# design.net
KiCad netlist of a schematic drawn in Altium Designer
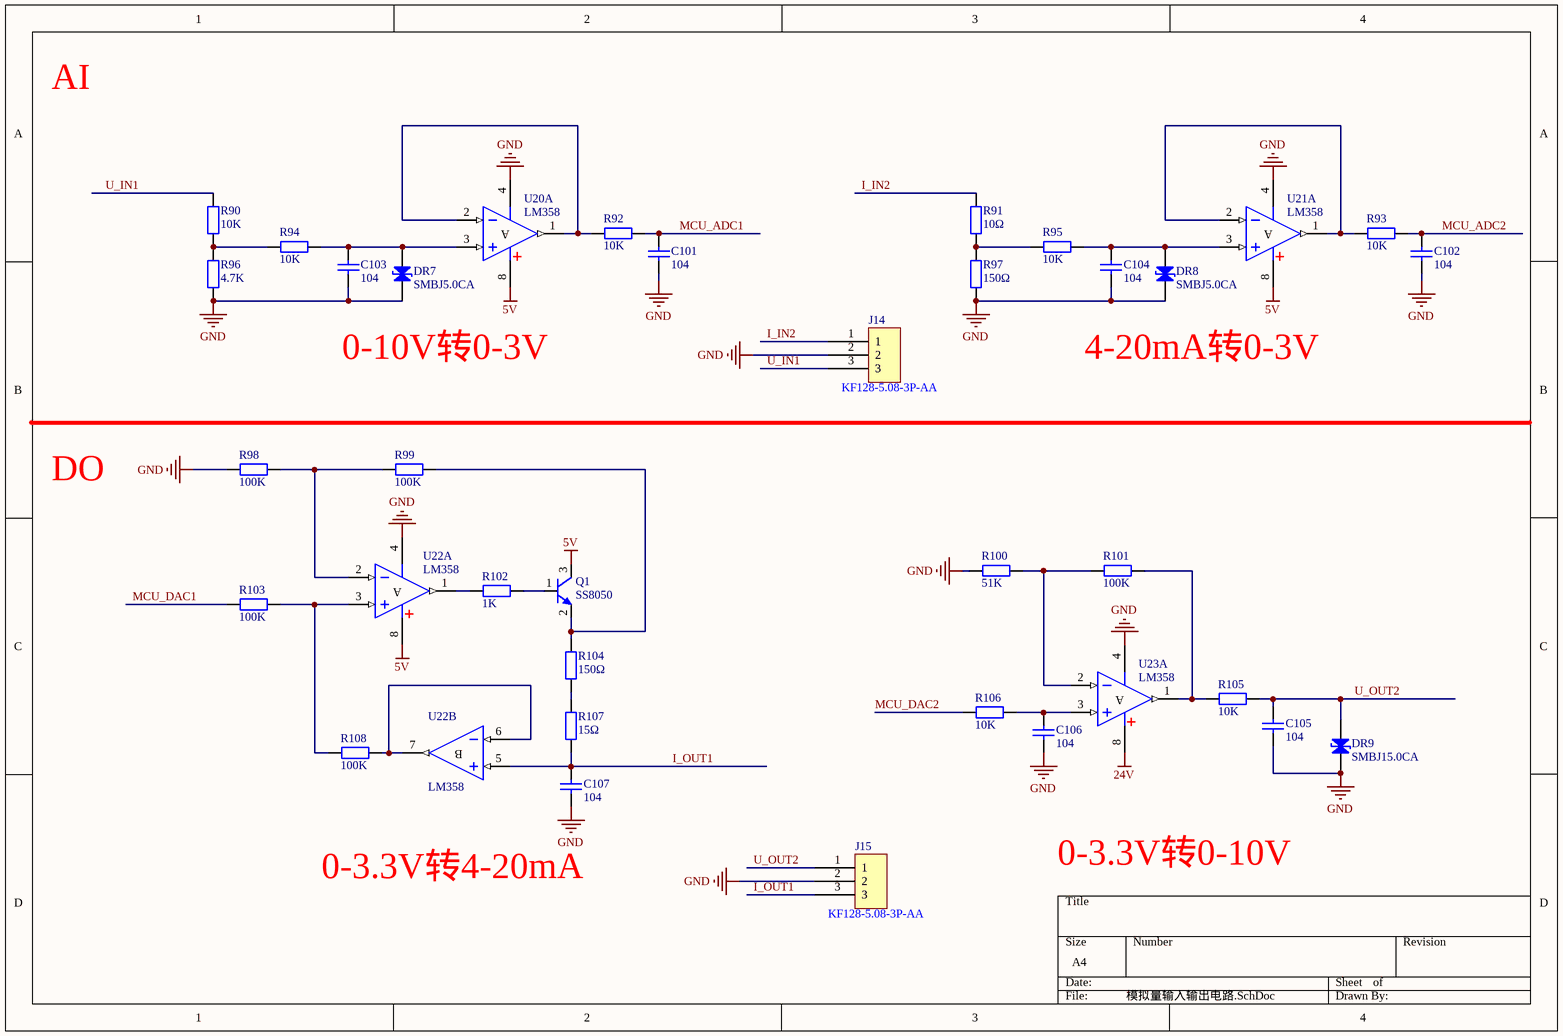
[diagram p0: 模拟量输入输出电路.SchDoc]

(export (version "E")
  (design (tool "Eeschema 10.0.6"))
  (components
    (comp (ref "C101")
      (value "104")
      (footprint "C 0603_L")
      (description "0603贴片电容")
      (fields (field (name "PUBLISHER") "Altium Limited"))
      (libsource (lib "STM32_PLC_20251215") (part "Cap"))
    )
    (comp (ref "C102")
      (value "104")
      (footprint "C 0603_L")
      (description "0603贴片电容")
      (fields (field (name "PUBLISHER") "Altium Limited"))
      (libsource (lib "STM32_PLC_20251215") (part "Cap"))
    )
    (comp (ref "C103")
      (value "104")
      (footprint "C 0603_L")
      (description "0603贴片电容")
      (fields (field (name "PUBLISHER") "Altium Limited"))
      (libsource (lib "STM32_PLC_20251215") (part "Cap"))
    )
    (comp (ref "C104")
      (value "104")
      (footprint "C 0603_L")
      (description "0603贴片电容")
      (fields (field (name "PUBLISHER") "Altium Limited"))
      (libsource (lib "STM32_PLC_20251215") (part "Cap"))
    )
    (comp (ref "C105")
      (value "104")
      (footprint "C 0603_L")
      (description "0603贴片电容")
      (fields (field (name "PUBLISHER") "Altium Limited"))
      (libsource (lib "STM32_PLC_20251215") (part "Cap"))
    )
    (comp (ref "C106")
      (value "104")
      (footprint "C 0603_L")
      (description "0603贴片电容")
      (fields (field (name "PUBLISHER") "Altium Limited"))
      (libsource (lib "STM32_PLC_20251215") (part "Cap"))
    )
    (comp (ref "C107")
      (value "104")
      (footprint "C 0603_L")
      (description "0603贴片电容")
      (fields (field (name "PUBLISHER") "Altium Limited"))
      (libsource (lib "STM32_PLC_20251215") (part "Cap"))
    )
    (comp (ref "DR7")
      (value "SMBJ5.0CA")
      (footprint "SMB")
      (description "SMA，瞬态电压抑制二极管")
      (fields (field (name "版权归属") "源创客"))
      (libsource (lib "STM32_PLC_20251215") (part "TVS"))
    )
    (comp (ref "DR8")
      (value "SMBJ5.0CA")
      (footprint "SMB")
      (description "SMA，瞬态电压抑制二极管")
      (fields (field (name "版权归属") "源创客"))
      (libsource (lib "STM32_PLC_20251215") (part "TVS"))
    )
    (comp (ref "DR9")
      (value "SMBJ15.0CA")
      (footprint "SMB")
      (description "SMA，瞬态电压抑制二极管")
      (fields (field (name "版权归属") "源创客"))
      (libsource (lib "STM32_PLC_20251215") (part "TVS"))
    )
    (comp (ref "J14")
      (value "KF128-5.08-3P-AA")
      (footprint "KF128-5.08-3P")
      (description "KF128-5.08-3P-AA端座")
      (fields (field (name "MANUFACTURER") "KEFA(科发)"))
      (libsource (lib "STM32_PLC_20251215") (part "KF128-5.08-3P-AA"))
    )
    (comp (ref "J15")
      (value "KF128-5.08-3P-AA")
      (footprint "KF128-5.08-3P")
      (description "KF128-5.08-3P-AA端座")
      (fields (field (name "MANUFACTURER") "KEFA(科发)"))
      (libsource (lib "STM32_PLC_20251215") (part "KF128-5.08-3P-AA"))
    )
    (comp (ref "Q1")
      (value "SS8050")
      (footprint "SOT-23_S8050")
      (description "NPN三极管")
      (fields (field (name "版权归属") "源创客"))
      (libsource (lib "STM32_PLC_20251215") (part "S8050"))
    )
    (comp (ref "R90")
      (value "10K")
      (footprint "R 0603_L")
      (description "C0603贴片电阻")
      (fields (field (name "版权归属") "源创客"))
      (libsource (lib "STM32_PLC_20251215") (part "Res"))
    )
    (comp (ref "R91")
      (value "10Ω")
      (footprint "R 0603_L")
      (description "C0603贴片电阻")
      (fields (field (name "版权归属") "源创客"))
      (libsource (lib "STM32_PLC_20251215") (part "Res"))
    )
    (comp (ref "R92")
      (value "10K")
      (footprint "R 0603_L")
      (description "C0603贴片电阻")
      (fields (field (name "版权归属") "源创客"))
      (libsource (lib "STM32_PLC_20251215") (part "Res"))
    )
    (comp (ref "R93")
      (value "10K")
      (footprint "R 0603_L")
      (description "C0603贴片电阻")
      (fields (field (name "版权归属") "源创客"))
      (libsource (lib "STM32_PLC_20251215") (part "Res"))
    )
    (comp (ref "R94")
      (value "10K")
      (footprint "R 0603_L")
      (description "C0603贴片电阻")
      (fields (field (name "版权归属") "源创客"))
      (libsource (lib "STM32_PLC_20251215") (part "Res"))
    )
    (comp (ref "R95")
      (value "10K")
      (footprint "R 0603_L")
      (description "C0603贴片电阻")
      (fields (field (name "版权归属") "源创客"))
      (libsource (lib "STM32_PLC_20251215") (part "Res"))
    )
    (comp (ref "R96")
      (value "4.7K")
      (footprint "R 0603_L")
      (description "C0603贴片电阻")
      (fields (field (name "版权归属") "源创客"))
      (libsource (lib "STM32_PLC_20251215") (part "Res"))
    )
    (comp (ref "R97")
      (value "150Ω")
      (footprint "R 0603_L")
      (description "C0603贴片电阻")
      (fields (field (name "版权归属") "源创客"))
      (libsource (lib "STM32_PLC_20251215") (part "Res"))
    )
    (comp (ref "R98")
      (value "100K")
      (footprint "R 0603_L")
      (description "C0603贴片电阻")
      (fields (field (name "版权归属") "源创客"))
      (libsource (lib "STM32_PLC_20251215") (part "Res"))
    )
    (comp (ref "R99")
      (value "100K")
      (footprint "R 0603_L")
      (description "C0603贴片电阻")
      (fields (field (name "版权归属") "源创客"))
      (libsource (lib "STM32_PLC_20251215") (part "Res"))
    )
    (comp (ref "R100")
      (value "51K")
      (footprint "R 0603_L")
      (description "C0603贴片电阻")
      (fields (field (name "版权归属") "源创客"))
      (libsource (lib "STM32_PLC_20251215") (part "Res"))
    )
    (comp (ref "R101")
      (value "100K")
      (footprint "R 0603_L")
      (description "C0603贴片电阻")
      (fields (field (name "版权归属") "源创客"))
      (libsource (lib "STM32_PLC_20251215") (part "Res"))
    )
    (comp (ref "R102")
      (value "1K")
      (footprint "R 0603_L")
      (description "C0603贴片电阻")
      (fields (field (name "版权归属") "源创客"))
      (libsource (lib "STM32_PLC_20251215") (part "Res"))
    )
    (comp (ref "R103")
      (value "100K")
      (footprint "R 0603_L")
      (description "C0603贴片电阻")
      (fields (field (name "版权归属") "源创客"))
      (libsource (lib "STM32_PLC_20251215") (part "Res"))
    )
    (comp (ref "R104")
      (value "150Ω")
      (footprint "R 0603_L")
      (description "0603贴片电阻")
      (fields (field (name "版权归属") "源创客"))
      (libsource (lib "STM32_PLC_20251215") (part "Res"))
    )
    (comp (ref "R105")
      (value "10K")
      (footprint "R 0603_L")
      (description "C0603贴片电阻")
      (fields (field (name "版权归属") "源创客"))
      (libsource (lib "STM32_PLC_20251215") (part "Res"))
    )
    (comp (ref "R106")
      (value "10K")
      (footprint "R 0603_L")
      (description "C0603贴片电阻")
      (fields (field (name "版权归属") "源创客"))
      (libsource (lib "STM32_PLC_20251215") (part "Res"))
    )
    (comp (ref "R107")
      (value "15Ω")
      (footprint "R 0603_L")
      (description "0603贴片电阻")
      (fields (field (name "版权归属") "源创客"))
      (libsource (lib "STM32_PLC_20251215") (part "Res"))
    )
    (comp (ref "R108")
      (value "100K")
      (footprint "R 0603_L")
      (description "C0603贴片电阻")
      (fields (field (name "版权归属") "源创客"))
      (libsource (lib "STM32_PLC_20251215") (part "Res"))
    )
    (comp (ref "U20")
      (value "LM358")
      (footprint "SOP8")
      (description "双路运放")
      (fields (field (name "版权归属") "源创客"))
      (libsource (lib "STM32_PLC_20251215") (part "LM358"))
    )
    (comp (ref "U21")
      (value "LM358")
      (footprint "SOP8")
      (description "双路运放")
      (fields (field (name "版权归属") "源创客"))
      (libsource (lib "STM32_PLC_20251215") (part "LM358"))
    )
    (comp (ref "U22")
      (value "LM358")
      (footprint "SOP8")
      (description "双路运放")
      (fields (field (name "版权归属") "源创客"))
      (libsource (lib "STM32_PLC_20251215") (part "LM358"))
    )
    (comp (ref "U23")
      (value "LM358")
      (footprint "SOP8")
      (description "双路运放")
      (fields (field (name "版权归属") "源创客"))
      (libsource (lib "STM32_PLC_20251215") (part "LM358"))
    )
  )
  (nets
    (net (code "1") (name "/I_IN2") (class "Default")
      (node (ref "J14") (pin "1") (pinfunction "1_1") (pintype "passive"))
      (node (ref "R91") (pin "2") (pinfunction "2_2") (pintype "passive"))
    )
    (net (code "2") (name "/I_OUT1") (class "Default")
      (node (ref "C107") (pin "2") (pinfunction "2_2") (pintype "passive"))
      (node (ref "J15") (pin "3") (pinfunction "3_3") (pintype "passive"))
      (node (ref "R107") (pin "2") (pinfunction "2_2") (pintype "passive"))
      (node (ref "U22") (pin "5") (pinfunction "IN+_5") (pintype "input"))
    )
    (net (code "3") (name "/MCU_ADC1") (class "Default")
      (node (ref "C101") (pin "2") (pinfunction "2_2") (pintype "passive"))
      (node (ref "R92") (pin "1") (pinfunction "1_1") (pintype "passive"))
    )
    (net (code "4") (name "/MCU_ADC2") (class "Default")
      (node (ref "C102") (pin "2") (pinfunction "2_2") (pintype "passive"))
      (node (ref "R93") (pin "1") (pinfunction "1_1") (pintype "passive"))
    )
    (net (code "5") (name "/MCU_DAC1") (class "Default")
      (node (ref "R103") (pin "2") (pinfunction "2_2") (pintype "passive"))
    )
    (net (code "6") (name "/MCU_DAC2") (class "Default")
      (node (ref "R106") (pin "2") (pinfunction "2_2") (pintype "passive"))
    )
    (net (code "7") (name "/U_IN1") (class "Default")
      (node (ref "J14") (pin "3") (pinfunction "3_3") (pintype "passive"))
      (node (ref "R90") (pin "2") (pinfunction "2_2") (pintype "passive"))
    )
    (net (code "8") (name "/U_OUT2") (class "Default")
      (node (ref "C105") (pin "2") (pinfunction "2_2") (pintype "passive"))
      (node (ref "DR9") (pin "1") (pinfunction "A_1") (pintype "passive"))
      (node (ref "J15") (pin "1") (pinfunction "1_1") (pintype "passive"))
      (node (ref "R105") (pin "1") (pinfunction "1_1") (pintype "passive"))
    )
    (net (code "9") (name "5V") (class "Default")
      (node (ref "Q1") (pin "3") (pinfunction "C_3") (pintype "passive"))
      (node (ref "U20") (pin "8") (pinfunction "V+_8") (pintype "power_in"))
      (node (ref "U21") (pin "8") (pinfunction "V+_8") (pintype "power_in"))
      (node (ref "U22") (pin "8") (pinfunction "V+_8") (pintype "power_in"))
    )
    (net (code "10") (name "24V") (class "Default")
      (node (ref "U23") (pin "8") (pinfunction "V+_8") (pintype "power_in"))
    )
    (net (code "11") (name "GND") (class "Default")
      (node (ref "C101") (pin "1") (pinfunction "1_1") (pintype "passive"))
      (node (ref "C102") (pin "1") (pinfunction "1_1") (pintype "passive"))
      (node (ref "C103") (pin "1") (pinfunction "1_1") (pintype "passive"))
      (node (ref "C104") (pin "1") (pinfunction "1_1") (pintype "passive"))
      (node (ref "C105") (pin "1") (pinfunction "1_1") (pintype "passive"))
      (node (ref "C106") (pin "1") (pinfunction "1_1") (pintype "passive"))
      (node (ref "C107") (pin "1") (pinfunction "1_1") (pintype "passive"))
      (node (ref "DR7") (pin "2") (pinfunction "K_2") (pintype "passive"))
      (node (ref "DR8") (pin "2") (pinfunction "K_2") (pintype "passive"))
      (node (ref "DR9") (pin "2") (pinfunction "K_2") (pintype "passive"))
      (node (ref "J14") (pin "2") (pinfunction "2_2") (pintype "passive"))
      (node (ref "J15") (pin "2") (pinfunction "2_2") (pintype "passive"))
      (node (ref "R100") (pin "2") (pinfunction "2_2") (pintype "passive"))
      (node (ref "R96") (pin "1") (pinfunction "1_1") (pintype "passive"))
      (node (ref "R97") (pin "1") (pinfunction "1_1") (pintype "passive"))
      (node (ref "R98") (pin "2") (pinfunction "2_2") (pintype "passive"))
      (node (ref "U20") (pin "4") (pinfunction "V-_4") (pintype "power_in"))
      (node (ref "U21") (pin "4") (pinfunction "V-_4") (pintype "power_in"))
      (node (ref "U22") (pin "4") (pinfunction "V-_4") (pintype "power_in"))
      (node (ref "U23") (pin "4") (pinfunction "V-_4") (pintype "power_in"))
    )
    (net (code "12") (name "Net-(DR7-A)") (class "Default")
      (node (ref "C103") (pin "2") (pinfunction "2_2") (pintype "passive"))
      (node (ref "DR7") (pin "1") (pinfunction "A_1") (pintype "passive"))
      (node (ref "R94") (pin "1") (pinfunction "1_1") (pintype "passive"))
      (node (ref "U20") (pin "3") (pinfunction "IN+_3") (pintype "input"))
    )
    (net (code "13") (name "Net-(DR8-A)") (class "Default")
      (node (ref "C104") (pin "2") (pinfunction "2_2") (pintype "passive"))
      (node (ref "DR8") (pin "1") (pinfunction "A_1") (pintype "passive"))
      (node (ref "R95") (pin "1") (pinfunction "1_1") (pintype "passive"))
      (node (ref "U21") (pin "3") (pinfunction "IN+_3") (pintype "input"))
    )
    (net (code "14") (name "Net-(Q1-B)") (class "Default")
      (node (ref "Q1") (pin "1") (pinfunction "B_1") (pintype "passive"))
      (node (ref "R102") (pin "1") (pinfunction "1_1") (pintype "passive"))
    )
    (net (code "15") (name "Net-(Q1-E)") (class "Default")
      (node (ref "Q1") (pin "2") (pinfunction "E_2") (pintype "passive"))
      (node (ref "R104") (pin "1") (pinfunction "1_1") (pintype "passive"))
      (node (ref "R99") (pin "1") (pinfunction "1_1") (pintype "passive"))
    )
    (net (code "16") (name "Net-(R90-Pad1)") (class "Default")
      (node (ref "R90") (pin "1") (pinfunction "1_1") (pintype "passive"))
      (node (ref "R94") (pin "2") (pinfunction "2_2") (pintype "passive"))
      (node (ref "R96") (pin "2") (pinfunction "2_2") (pintype "passive"))
    )
    (net (code "17") (name "Net-(R91-Pad1)") (class "Default")
      (node (ref "R91") (pin "1") (pinfunction "1_1") (pintype "passive"))
      (node (ref "R95") (pin "2") (pinfunction "2_2") (pintype "passive"))
      (node (ref "R97") (pin "2") (pinfunction "2_2") (pintype "passive"))
    )
    (net (code "18") (name "Net-(R104-Pad2)") (class "Default")
      (node (ref "R104") (pin "2") (pinfunction "2_2") (pintype "passive"))
      (node (ref "R107") (pin "1") (pinfunction "1_1") (pintype "passive"))
    )
    (net (code "19") (name "Net-(U20A-IN-)") (class "Default")
      (node (ref "R92") (pin "2") (pinfunction "2_2") (pintype "passive"))
      (node (ref "U20") (pin "1") (pinfunction "OUT_1") (pintype "output"))
      (node (ref "U20") (pin "2") (pinfunction "IN-_2") (pintype "input"))
    )
    (net (code "20") (name "Net-(U21A-IN-)") (class "Default")
      (node (ref "R93") (pin "2") (pinfunction "2_2") (pintype "passive"))
      (node (ref "U21") (pin "1") (pinfunction "OUT_1") (pintype "output"))
      (node (ref "U21") (pin "2") (pinfunction "IN-_2") (pintype "input"))
    )
    (net (code "21") (name "Net-(U22A-IN+)") (class "Default")
      (node (ref "R103") (pin "1") (pinfunction "1_1") (pintype "passive"))
      (node (ref "R108") (pin "2") (pinfunction "2_2") (pintype "passive"))
      (node (ref "U22") (pin "3") (pinfunction "IN+_3") (pintype "input"))
    )
    (net (code "22") (name "Net-(U22A-IN-)") (class "Default")
      (node (ref "R98") (pin "1") (pinfunction "1_1") (pintype "passive"))
      (node (ref "R99") (pin "2") (pinfunction "2_2") (pintype "passive"))
      (node (ref "U22") (pin "2") (pinfunction "IN-_2") (pintype "input"))
    )
    (net (code "23") (name "Net-(U22A-OUT)") (class "Default")
      (node (ref "R102") (pin "2") (pinfunction "2_2") (pintype "passive"))
      (node (ref "U22") (pin "1") (pinfunction "OUT_1") (pintype "output"))
    )
    (net (code "24") (name "Net-(U22B-IN-)") (class "Default")
      (node (ref "R108") (pin "1") (pinfunction "1_1") (pintype "passive"))
      (node (ref "U22") (pin "6") (pinfunction "IN-_6") (pintype "input"))
      (node (ref "U22") (pin "7") (pinfunction "OUT_7") (pintype "output"))
    )
    (net (code "25") (name "Net-(U23A-IN+)") (class "Default")
      (node (ref "C106") (pin "2") (pinfunction "2_2") (pintype "passive"))
      (node (ref "R106") (pin "1") (pinfunction "1_1") (pintype "passive"))
      (node (ref "U23") (pin "3") (pinfunction "IN+_3") (pintype "input"))
    )
    (net (code "26") (name "Net-(U23A-IN-)") (class "Default")
      (node (ref "R100") (pin "1") (pinfunction "1_1") (pintype "passive"))
      (node (ref "R101") (pin "2") (pinfunction "2_2") (pintype "passive"))
      (node (ref "U23") (pin "2") (pinfunction "IN-_2") (pintype "input"))
    )
    (net (code "27") (name "Net-(U23A-OUT)") (class "Default")
      (node (ref "R101") (pin "1") (pinfunction "1_1") (pintype "passive"))
      (node (ref "R105") (pin "2") (pinfunction "2_2") (pintype "passive"))
      (node (ref "U23") (pin "1") (pinfunction "OUT_1") (pintype "output"))
    )
  )
)
